# 2_PowerRails.net
KiCad netlist of a schematic drawn in Altium Designer
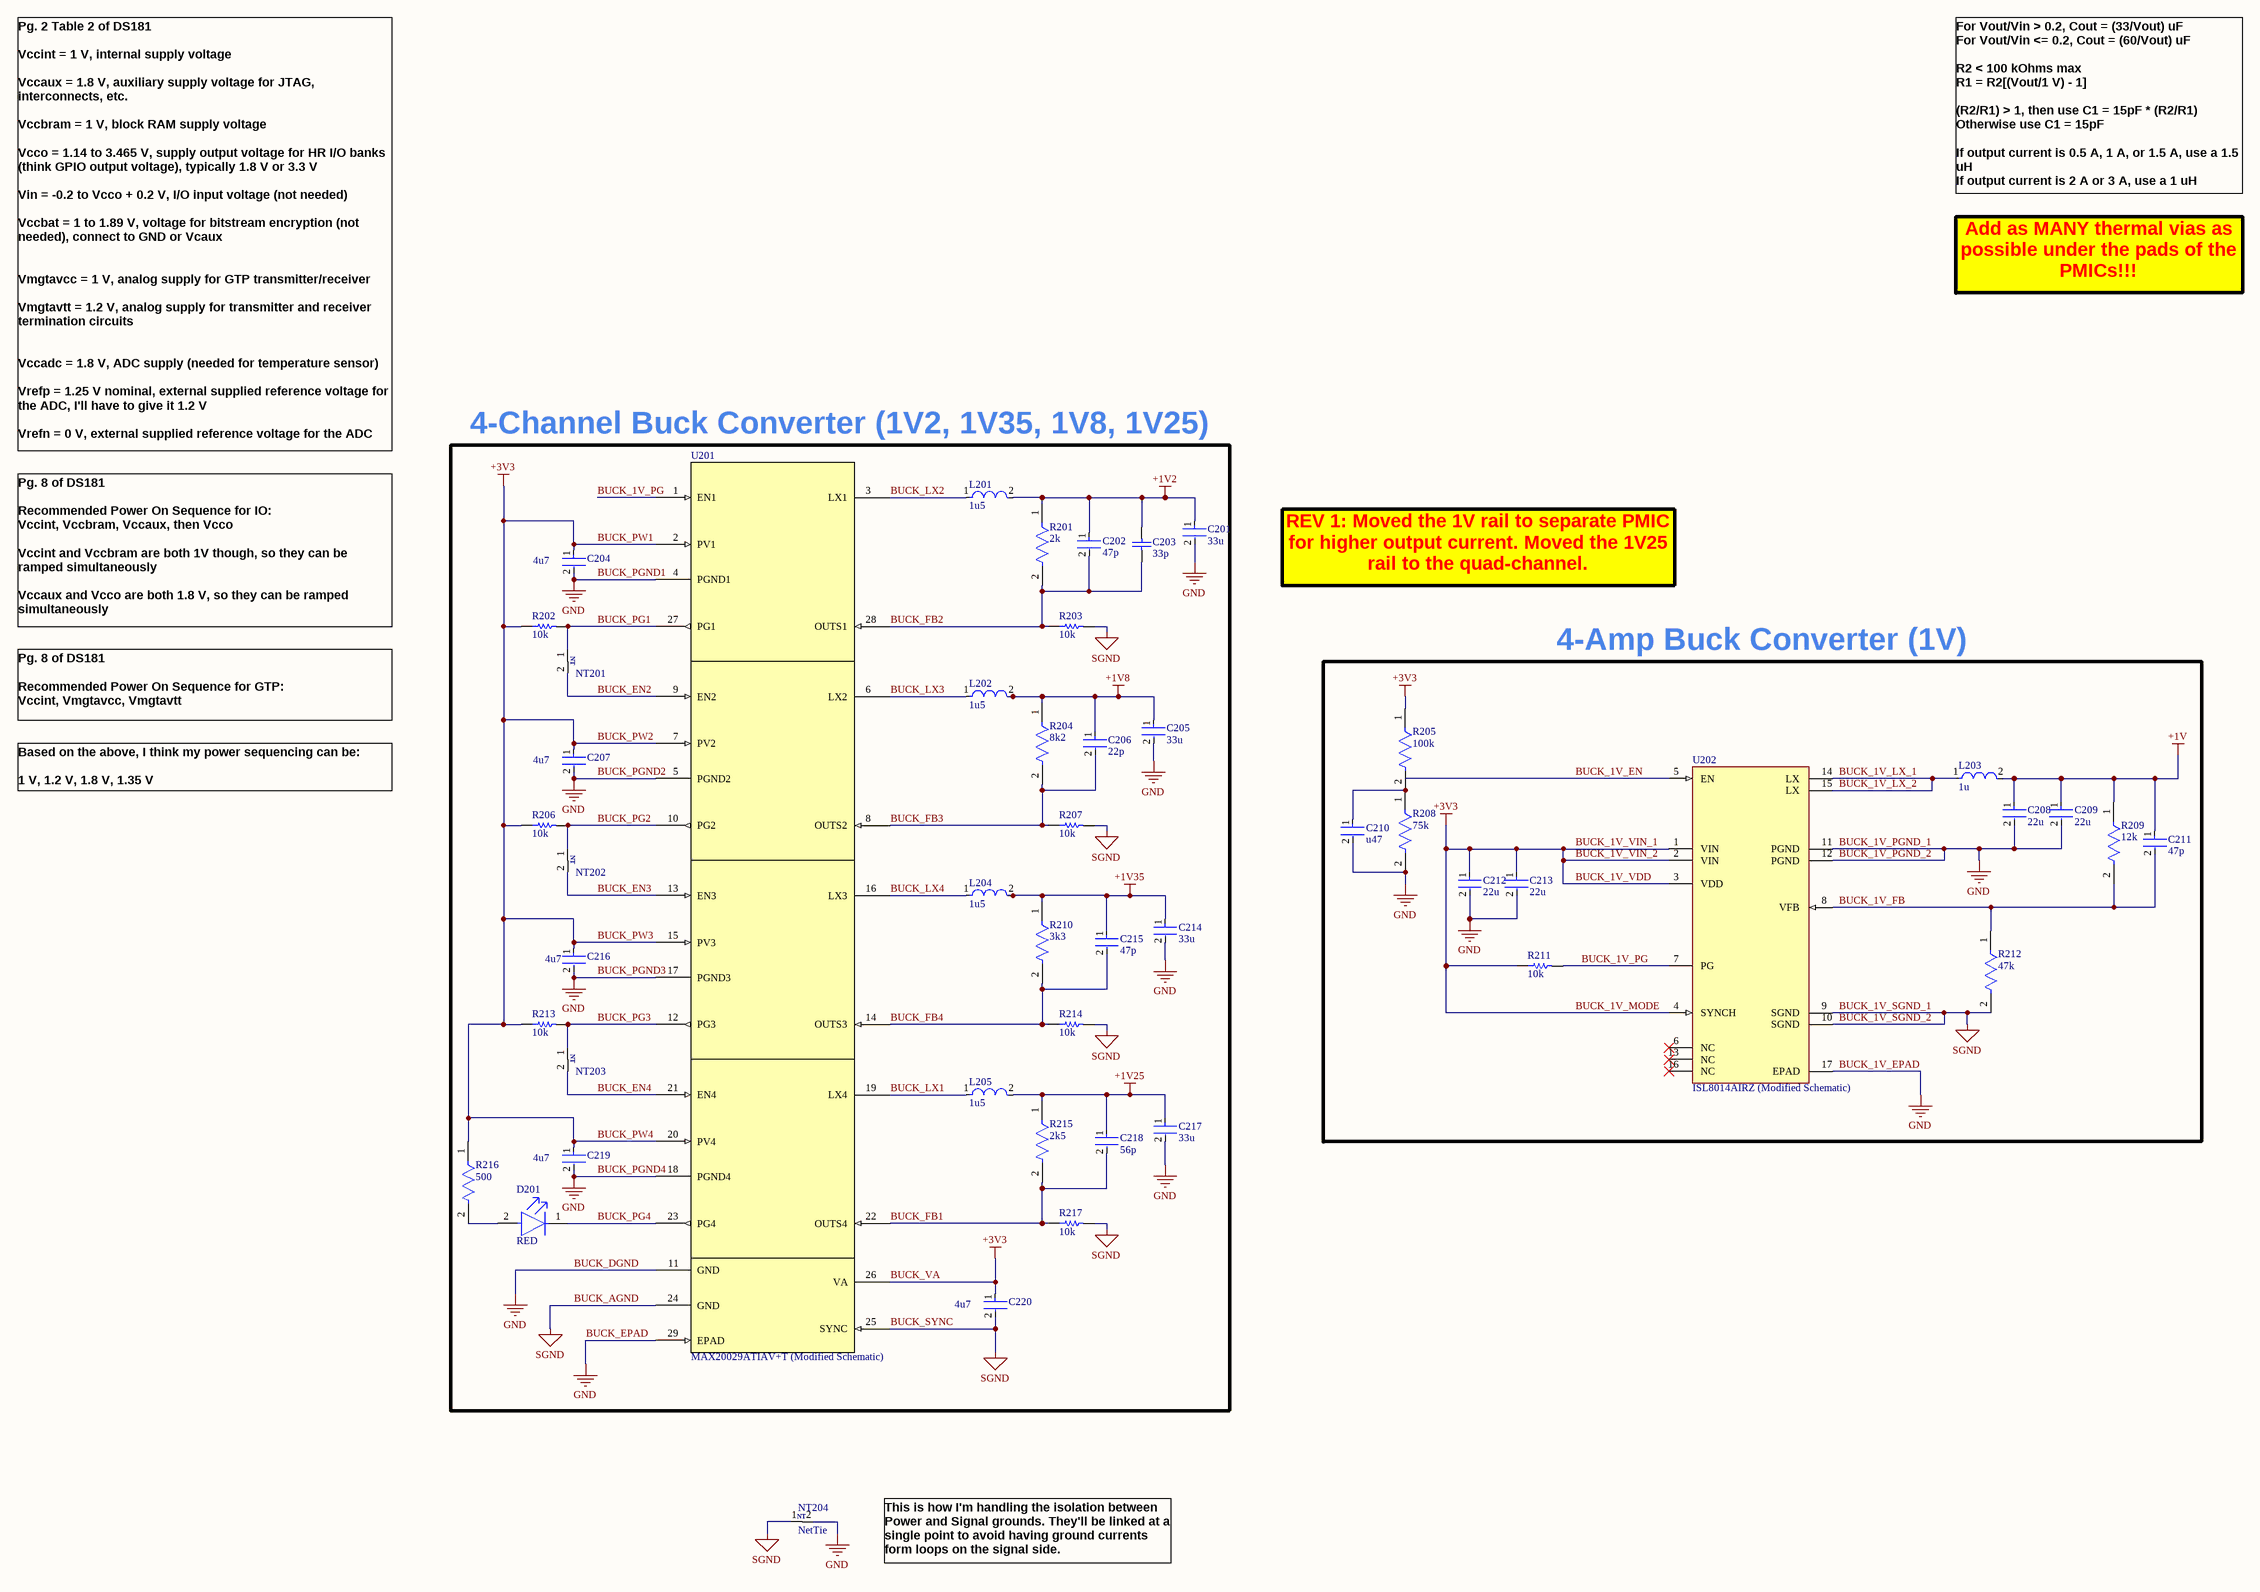
[diagram p0: 2_PowerRails.SchDoc]

(export (version "E")
  (design (tool "Eeschema 10.0.6"))
  (components
    (comp (ref "C201")
      (value "33u")
      (footprint "FP-C2012-125-0_2-IPC_A")
      (description "C2012X5R1A336M125AC\r\n\r\nMultilayer Ceramic Capacitors 33μF ±20% 10V X5R SMD 0805")
      (fields (field (name "TOLERANCE") "20%"))
      (libsource (lib "Altium Content Vault") (part "b4654b650e69147ec39a6b967a45e02"))
    )
    (comp (ref "C202")
      (value "47p")
      (footprint "FP-GCQ155-0_05-MFG")
      (libsource (lib "Altium Content Vault") (part "02cd4be3c70576c341d710602a673aa"))
    )
    (comp (ref "C203")
      (value "33p")
      (footprint "CAPC1005X60X26NL10T16")
      (description "VJ0402A330JXAAC")
      (fields (field (name "MANUFACTURER") "Vitramon"))
      (libsource (lib "Altium Content Vault") (part "CAP"))
    )
    (comp (ref "C204")
      (value "4u7")
      (footprint "FP-GCM31C-0_2-e0_3_0_8-IPC_C")
      (description "GCM31CR71E475KA55K\r\n\r\nCeramic Capacitor for Automotive 4.7uF ±10% 25VDC X7R 1206 Embossed T/R")
      (fields (field (name "TOLERANCE") "10%"))
      (libsource (lib "Altium Content Vault") (part "11868f565c42a9108669ba33697ecf6"))
    )
    (comp (ref "C205")
      (value "33u")
      (footprint "FP-C2012-125-0_2-IPC_A")
      (description "C2012X5R1A336M125AC\r\n\r\nMultilayer Ceramic Capacitors 33μF ±20% 10V X5R SMD 0805")
      (fields (field (name "TOLERANCE") "20%"))
      (libsource (lib "Altium Content Vault") (part "b4654b650e69147ec39a6b967a45e02"))
    )
    (comp (ref "C206")
      (value "22p")
      (footprint "FP-GJM155-0_05-IPC_A")
      (description "GJM1555C1H220GB01D\r\n\r\nMulti-Layer Ceramic Capacitor 22pF C0G  ±2% 0402 Paper T/R")
      (fields (field (name "TOLERANCE") "2%"))
      (libsource (lib "Altium Content Vault") (part "02cd4be3c70576c341d710602a673aa"))
    )
    (comp (ref "C207")
      (value "4u7")
      (footprint "FP-GCM31C-0_2-e0_3_0_8-IPC_C")
      (description "GCM31CR71E475KA55K\r\n\r\nCeramic Capacitor for Automotive 4.7uF ±10% 25VDC X7R 1206 Embossed T/R")
      (fields (field (name "TOLERANCE") "10%"))
      (libsource (lib "Altium Content Vault") (part "11868f565c42a9108669ba33697ecf6"))
    )
    (comp (ref "C208")
      (value "22u")
      (footprint "FP-GRM188-0_2-IPC_A")
      (description "GRM188R61C226ME01D\r\n\r\nMultilayer Ceramic Capacitor 22uF 20% 16V X5R 0603 Paper T/R")
      (libsource (lib "Altium Content Vault") (part "02cd4be3c70576c341d710602a673aa"))
    )
    (comp (ref "C209")
      (value "22u")
      (footprint "FP-GRM188-0_2-IPC_A")
      (description "GRM188R61C226ME01D\r\n\r\nMultilayer Ceramic Capacitor 22uF 20% 16V X5R 0603 Paper T/R")
      (libsource (lib "Altium Content Vault") (part "02cd4be3c70576c341d710602a673aa"))
    )
    (comp (ref "C210")
      (value "u47")
      (footprint "FP-C0603-030-0_03-IPC_A")
      (description "C0603X5R1A474M030BC\r\n\r\nMultilayer Ceramic Capacitors 470nF ±20% 10V X5R SMD 0201")
      (fields (field (name "TOLERANCE") "20%"))
      (libsource (lib "Altium Content Vault") (part "02cd4be3c70576c341d710602a673aa"))
    )
    (comp (ref "C211")
      (value "47p")
      (footprint "FP-GCQ155-0_05-MFG")
      (libsource (lib "Altium Content Vault") (part "02cd4be3c70576c341d710602a673aa"))
    )
    (comp (ref "C212")
      (value "22u")
      (footprint "FP-GRM188-0_2-IPC_A")
      (description "GRM188R61C226ME01D\r\n\r\nMultilayer Ceramic Capacitor 22uF 20% 16V X5R 0603 Paper T/R")
      (libsource (lib "Altium Content Vault") (part "02cd4be3c70576c341d710602a673aa"))
    )
    (comp (ref "C213")
      (value "22u")
      (footprint "FP-GRM188-0_2-IPC_A")
      (description "GRM188R61C226ME01D\r\n\r\nMultilayer Ceramic Capacitor 22uF 20% 16V X5R 0603 Paper T/R")
      (libsource (lib "Altium Content Vault") (part "02cd4be3c70576c341d710602a673aa"))
    )
    (comp (ref "C214")
      (value "33u")
      (footprint "FP-C2012-125-0_2-IPC_A")
      (description "C2012X5R1A336M125AC\r\n\r\nMultilayer Ceramic Capacitors 33μF ±20% 10V X5R SMD 0805")
      (fields (field (name "TOLERANCE") "20%"))
      (libsource (lib "Altium Content Vault") (part "b4654b650e69147ec39a6b967a45e02"))
    )
    (comp (ref "C215")
      (value "47p")
      (footprint "FP-GCQ155-0_05-MFG")
      (libsource (lib "Altium Content Vault") (part "02cd4be3c70576c341d710602a673aa"))
    )
    (comp (ref "C216")
      (value "4u7")
      (footprint "FP-GCM31C-0_2-e0_3_0_8-IPC_C")
      (description "GCM31CR71E475KA55K\r\n\r\nCeramic Capacitor for Automotive 4.7uF ±10% 25VDC X7R 1206 Embossed T/R")
      (fields (field (name "TOLERANCE") "10%"))
      (libsource (lib "Altium Content Vault") (part "11868f565c42a9108669ba33697ecf6"))
    )
    (comp (ref "C217")
      (value "33u")
      (footprint "FP-C2012-125-0_2-IPC_A")
      (description "C2012X5R1A336M125AC\r\n\r\nMultilayer Ceramic Capacitors 33μF ±20% 10V X5R SMD 0805")
      (fields (field (name "TOLERANCE") "20%"))
      (libsource (lib "Altium Content Vault") (part "b4654b650e69147ec39a6b967a45e02"))
    )
    (comp (ref "C218")
      (value "56p")
      (footprint "FP-C0402-BB-MFG")
      (description "C0402 56 pF X8R 10.00% 50 V")
      (fields (field (name "MANUFACTURER PART NUMBER") "C0402C560K5HACTU"))
      (libsource (lib "Altium Content Vault") (part "b4654b650e69147ec39a6b967a45e02"))
    )
    (comp (ref "C219")
      (value "4u7")
      (footprint "FP-GCM31C-0_2-e0_3_0_8-IPC_C")
      (description "GCM31CR71E475KA55K\r\n\r\nCeramic Capacitor for Automotive 4.7uF ±10% 25VDC X7R 1206 Embossed T/R")
      (fields (field (name "TOLERANCE") "10%"))
      (libsource (lib "Altium Content Vault") (part "11868f565c42a9108669ba33697ecf6"))
    )
    (comp (ref "C220")
      (value "4u7")
      (footprint "FP-GCM31C-0_2-e0_3_0_8-IPC_C")
      (description "GCM31CR71E475KA55K\r\n\r\nCeramic Capacitor for Automotive 4.7uF ±10% 25VDC X7R 1206 Embossed T/R")
      (fields (field (name "TOLERANCE") "10%"))
      (libsource (lib "Altium Content Vault") (part "11868f565c42a9108669ba33697ecf6"))
    )
    (comp (ref "D201")
      (value "RED")
      (footprint "FP-SML-LX0603SIW-TR-MFG")
      (description "SML-LX0603SIW-TR\r\n\r\nLED RED DIFFUSED SMD")
      (libsource (lib "Altium Content Vault") (part "8706943c75ba83719d021d2fdc84c58"))
    )
    (comp (ref "L201")
      (value "1u5")
      (footprint "FP-IHLP-2525CZ-FP_2_413x3-MFG")
      (fields (field (name "TOLERANCE") "20%"))
      (libsource (lib "Altium Content Vault") (part "725321dda6339637d4d059423bc1c3c"))
    )
    (comp (ref "L202")
      (value "1u5")
      (footprint "FP-IHLP-2525CZ-FP_2_413x3-MFG")
      (fields (field (name "TOLERANCE") "20%"))
      (libsource (lib "Altium Content Vault") (part "725321dda6339637d4d059423bc1c3c"))
    )
    (comp (ref "L203")
      (value "1u")
      (footprint "FP-IHLP-2525CZ-FP_2_413x3-MFG")
      (fields (field (name "TOLERANCE") "20%"))
      (libsource (lib "Altium Content Vault") (part "725321dda6339637d4d059423bc1c3c"))
    )
    (comp (ref "L204")
      (value "1u5")
      (footprint "FP-IHLP-2525CZ-FP_2_413x3-MFG")
      (fields (field (name "TOLERANCE") "20%"))
      (libsource (lib "Altium Content Vault") (part "725321dda6339637d4d059423bc1c3c"))
    )
    (comp (ref "L205")
      (value "1u5")
      (footprint "FP-IHLP-2525CZ-FP_2_413x3-MFG")
      (fields (field (name "TOLERANCE") "20%"))
      (libsource (lib "Altium Content Vault") (part "725321dda6339637d4d059423bc1c3c"))
    )
    (comp (ref "NT201")
      (value "NetTie")
      (footprint "NETTIE")
      (description "Net Tie")
      (fields (field (name "SOURCE") "Schematic-Lib-PhilsLab.SchLib"))
      (libsource (lib "Withanage Perera") (part "NetTie"))
    )
    (comp (ref "NT202")
      (value "NetTie")
      (footprint "NETTIE")
      (description "Net Tie")
      (fields (field (name "SOURCE") "Schematic-Lib-PhilsLab.SchLib"))
      (libsource (lib "Withanage Perera") (part "NetTie"))
    )
    (comp (ref "NT203")
      (value "NetTie")
      (footprint "NETTIE")
      (description "Net Tie")
      (fields (field (name "SOURCE") "Schematic-Lib-PhilsLab.SchLib"))
      (libsource (lib "Withanage Perera") (part "NetTie"))
    )
    (comp (ref "NT204")
      (value "NetTie")
      (footprint "NETTIE")
      (description "Net Tie")
      (fields (field (name "SOURCE") "Schematic-Lib-PhilsLab.SchLib"))
      (libsource (lib "Withanage Perera") (part "NetTie"))
    )
    (comp (ref "R201")
      (value "2k")
      (footprint "FP-MCS0402-IPC_A")
      (description "MCS0402MD2001BE100\r\n\r\nRES SMD 1.2K OHM 1% 1/10W 0402")
      (fields (field (name "TOLERANCE") "0.1%"))
      (libsource (lib "Altium Content Vault") (part "1029c3af85768c4190bb7ad29bc67b5"))
    )
    (comp (ref "R202")
      (value "10k")
      (footprint "RESC1005X40X25LL10T10")
      (description "SG73P1ETTP1002F")
      (fields (field (name "MANUFACTURER") "KOA Speer"))
      (libsource (lib "Altium Content Vault") (part "RES"))
    )
    (comp (ref "R203")
      (value "10k")
      (footprint "RESC1005X40X25LL10T10")
      (description "SG73P1ETTP1002F")
      (fields (field (name "MANUFACTURER") "KOA Speer"))
      (libsource (lib "Altium Content Vault") (part "RES"))
    )
    (comp (ref "R204")
      (value "8k2")
      (footprint "FP-ERA2A-MFG")
      (description "ERA-2AEB822X\r\n\r\nRES SMD 8.2K OHM 0.1% 1/16W 0402")
      (fields
        (field (name "MANUFACTURER") "Panasonic Electronic Components")
        (field (name "OCTOPART") "https://octopart.com/era-2aeb822x-panasonic-43284358")
      )
      (libsource (lib "Altium Content Vault") (part "1029c3af85768c4190bb7ad29bc67b5"))
    )
    (comp (ref "R205")
      (value "100k")
      (footprint "FP-MCS0402-MFG")
      (description "MCS04020D1003BE000\r\n\r\nRES SMD 1.2K OHM 1% 1/10W 0402")
      (fields (field (name "TOLERANCE") "0.1%"))
      (libsource (lib "Altium Content Vault") (part "1029c3af85768c4190bb7ad29bc67b5"))
    )
    (comp (ref "R206")
      (value "10k")
      (footprint "RESC1005X40X25LL10T10")
      (description "SG73P1ETTP1002F")
      (fields (field (name "MANUFACTURER") "KOA Speer"))
      (libsource (lib "Altium Content Vault") (part "RES"))
    )
    (comp (ref "R207")
      (value "10k")
      (footprint "RESC1005X40X25LL10T10")
      (description "SG73P1ETTP1002F")
      (fields (field (name "MANUFACTURER") "KOA Speer"))
      (libsource (lib "Altium Content Vault") (part "RES"))
    )
    (comp (ref "R208")
      (value "75k")
      (footprint "FP-CR0402-IPC_C")
      (description "CR0402-FX-7502GLF\r\n\r\nThick Film Chip Resistors 0402 75kΩ 0.0625W 1% 100ppm/°C")
      (fields (field (name "TOLERANCE") "1%"))
      (libsource (lib "Altium Content Vault") (part "1029c3af85768c4190bb7ad29bc67b5"))
    )
    (comp (ref "R209")
      (value "12k")
      (footprint "FP-RT0402-MFG")
      (description "RT0402 12KΩ 0.063W 50 ppm/°C 0.50%")
      (fields (field (name "OCTOPART") "https://octopart.com/rt0402dre0712kl-yageo-1393491"))
      (libsource (lib "Altium Content Vault") (part "1029c3af85768c4190bb7ad29bc67b5"))
    )
    (comp (ref "R210")
      (value "3k3")
      (footprint "FP-ERA2A-MFG")
      (description "ERA-2AEB332X")
      (fields (field (name "TOLERANCE") "0.1%"))
      (libsource (lib "Altium Content Vault") (part "1029c3af85768c4190bb7ad29bc67b5"))
    )
    (comp (ref "R211")
      (value "10k")
      (footprint "RESC1005X40X25LL10T10")
      (description "SG73P1ETTP1002F")
      (fields (field (name "MANUFACTURER") "KOA Speer"))
      (libsource (lib "Altium Content Vault") (part "RES"))
    )
    (comp (ref "R212")
      (value "47k")
      (footprint "FP-ERA2A-MFG")
      (description "ERA-2AEB473X")
      (fields (field (name "TOLERANCE") "0.1%"))
      (libsource (lib "Altium Content Vault") (part "1029c3af85768c4190bb7ad29bc67b5"))
    )
    (comp (ref "R213")
      (value "10k")
      (footprint "RESC1005X40X25LL10T10")
      (description "SG73P1ETTP1002F")
      (fields (field (name "MANUFACTURER") "KOA Speer"))
      (libsource (lib "Altium Content Vault") (part "RES"))
    )
    (comp (ref "R214")
      (value "10k")
      (footprint "RESC1005X40X25LL10T10")
      (description "SG73P1ETTP1002F")
      (fields (field (name "MANUFACTURER") "KOA Speer"))
      (libsource (lib "Altium Content Vault") (part "RES"))
    )
    (comp (ref "R215")
      (value "2k5")
      (footprint "FP-MCT0603-MFG")
      (description "MCT06030E2501BP100\r\n\r\nRES SMD 100 OHM 1% 1/8W 0603")
      (fields (field (name "TOLERANCE") "0.1%"))
      (libsource (lib "Altium Content Vault") (part "1029c3af85768c4190bb7ad29bc67b5"))
    )
    (comp (ref "R216")
      (value "500")
      (footprint "FP-PNM0402-MFG")
      (description "PNM0402E5000BST1\r\n\r\nRES SMD 500 OHM 0.1% 1/20W 0402")
      (fields (field (name "TOLERANCE") "0.1%"))
      (libsource (lib "Altium Content Vault") (part "1029c3af85768c4190bb7ad29bc67b5"))
    )
    (comp (ref "R217")
      (value "10k")
      (footprint "RESC1005X40X25LL10T10")
      (description "SG73P1ETTP1002F")
      (fields (field (name "MANUFACTURER") "KOA Speer"))
      (libsource (lib "Altium Content Vault") (part "RES"))
    )
    (comp (ref "U201")
      (value "MAX20029ATIAV+T (Modified Schematic)")
      (footprint "21-0140L_T2855-5_MXM")
      (description "Automotive Quad/Triple Low-Voltage Step-Down DC-DC Converters")
      (fields
        (field (name "MANUFACTURER_PART_NUMBER") "MAX20029ATIA/V+T")
        (field (name "COPYRIGHT") "Copyright (C) 2025 Ultra Librarian. All rights reserved.")
      )
      (libsource (lib "Withanage Perera") (part "MAX20029ATIAV+T"))
    )
    (comp (ref "U202")
      (value "ISL8014AIRZ (Modified Schematic)")
      (footprint "QFN65P400X400X100-17_L16_4x4_M")
      (description "ISL8014 Series 2.8 - 5.5 V 1 MHz 4 A Buck Regulator - QFN-16")
      (libsource (lib "Withanage Perera") (part "6273e654be0da227d358b1ef3a404fb"))
    )
  )
  (nets
    (net (code "1") (name "+1V") (class "Default")
      (node (ref "C208") (pin "1") (pinfunction "1_1") (pintype "passive"))
      (node (ref "C209") (pin "1") (pinfunction "1_1") (pintype "passive"))
      (node (ref "C211") (pin "1") (pinfunction "1_1") (pintype "passive"))
      (node (ref "L203") (pin "2") (pinfunction "2_2") (pintype "passive"))
      (node (ref "R209") (pin "1") (pinfunction "1_1") (pintype "passive"))
    )
    (net (code "2") (name "+1V2") (class "Default")
      (node (ref "C201") (pin "1") (pinfunction "1_1") (pintype "passive"))
      (node (ref "C202") (pin "1") (pinfunction "1_1") (pintype "passive"))
      (node (ref "C203") (pin "2") (pinfunction "2_2") (pintype "passive"))
      (node (ref "L201") (pin "2") (pinfunction "2_2") (pintype "passive"))
      (node (ref "R201") (pin "1") (pinfunction "1_1") (pintype "passive"))
    )
    (net (code "3") (name "+1V8") (class "Default")
      (node (ref "C205") (pin "1") (pinfunction "1_1") (pintype "passive"))
      (node (ref "C206") (pin "1") (pinfunction "1_1") (pintype "passive"))
      (node (ref "L202") (pin "2") (pinfunction "2_2") (pintype "passive"))
      (node (ref "R204") (pin "1") (pinfunction "1_1") (pintype "passive"))
    )
    (net (code "4") (name "+1V25") (class "Default")
      (node (ref "C217") (pin "1") (pinfunction "1_1") (pintype "passive"))
      (node (ref "C218") (pin "1") (pinfunction "1_1") (pintype "passive"))
      (node (ref "L205") (pin "2") (pinfunction "2_2") (pintype "passive"))
      (node (ref "R215") (pin "1") (pinfunction "1_1") (pintype "passive"))
    )
    (net (code "5") (name "+1V35") (class "Default")
      (node (ref "C214") (pin "1") (pinfunction "1_1") (pintype "passive"))
      (node (ref "C215") (pin "1") (pinfunction "1_1") (pintype "passive"))
      (node (ref "L204") (pin "2") (pinfunction "2_2") (pintype "passive"))
      (node (ref "R210") (pin "1") (pinfunction "1_1") (pintype "passive"))
    )
    (net (code "6") (name "+3V3") (class "Default")
      (node (ref "C204") (pin "1") (pinfunction "1_1") (pintype "passive"))
      (node (ref "C207") (pin "1") (pinfunction "1_1") (pintype "passive"))
      (node (ref "C212") (pin "1") (pinfunction "1_1") (pintype "passive"))
      (node (ref "C213") (pin "1") (pinfunction "1_1") (pintype "passive"))
      (node (ref "C216") (pin "1") (pinfunction "1_1") (pintype "passive"))
      (node (ref "C219") (pin "1") (pinfunction "1_1") (pintype "passive"))
      (node (ref "C220") (pin "1") (pinfunction "1_1") (pintype "passive"))
      (node (ref "R202") (pin "1") (pinfunction "1_1") (pintype "passive"))
      (node (ref "R205") (pin "1") (pinfunction "1_1") (pintype "passive"))
      (node (ref "R206") (pin "1") (pinfunction "1_1") (pintype "passive"))
      (node (ref "R211") (pin "1") (pinfunction "1_1") (pintype "passive"))
      (node (ref "R213") (pin "1") (pinfunction "1_1") (pintype "passive"))
      (node (ref "R216") (pin "1") (pinfunction "1_1") (pintype "passive"))
      (node (ref "U201") (pin "15") (pinfunction "PV3_15") (pintype "input"))
      (node (ref "U201") (pin "2") (pinfunction "PV1_2") (pintype "input"))
      (node (ref "U201") (pin "20") (pinfunction "PV4_20") (pintype "input"))
      (node (ref "U201") (pin "26") (pinfunction "VA_26") (pintype "passive"))
      (node (ref "U201") (pin "7") (pinfunction "PV2_7") (pintype "input"))
      (node (ref "U202") (pin "1") (pinfunction "VIN_1") (pintype "power_in"))
      (node (ref "U202") (pin "2") (pinfunction "VIN_2") (pintype "power_in"))
      (node (ref "U202") (pin "3") (pinfunction "VDD_3") (pintype "power_in"))
      (node (ref "U202") (pin "4") (pinfunction "SYNCH_4") (pintype "input"))
    )
    (net (code "7") (name "/BUCK_1V_EN") (class "Default")
      (node (ref "U202") (pin "5") (pinfunction "EN_5") (pintype "input"))
    )
    (net (code "8") (name "/BUCK_1V_FB") (class "Default")
      (node (ref "C211") (pin "2") (pinfunction "2_2") (pintype "passive"))
      (node (ref "R209") (pin "2") (pinfunction "2_2") (pintype "passive"))
      (node (ref "R212") (pin "1") (pinfunction "1_1") (pintype "passive"))
      (node (ref "U202") (pin "8") (pinfunction "VFB_8") (pintype "input"))
    )
    (net (code "9") (name "/BUCK_1V_LX_1") (class "Default")
      (node (ref "L203") (pin "1") (pinfunction "1_1") (pintype "passive"))
      (node (ref "U202") (pin "14") (pinfunction "LX_14") (pintype "passive"))
      (node (ref "U202") (pin "15") (pinfunction "LX_15") (pintype "passive"))
    )
    (net (code "10") (name "/BUCK_1V_PG") (class "Default")
      (node (ref "R211") (pin "2") (pinfunction "2_2") (pintype "passive"))
      (node (ref "U201") (pin "1") (pinfunction "EN1_1") (pintype "input"))
      (node (ref "U202") (pin "7") (pinfunction "PG_7") (pintype "open_collector"))
    )
    (net (code "11") (name "/BUCK_EN2") (class "Default")
      (node (ref "NT201") (pin "2") (pinfunction "2_2") (pintype "passive"))
      (node (ref "U201") (pin "9") (pinfunction "EN2_9") (pintype "input"))
    )
    (net (code "12") (name "/BUCK_EN3") (class "Default")
      (node (ref "NT202") (pin "2") (pinfunction "2_2") (pintype "passive"))
      (node (ref "U201") (pin "13") (pinfunction "EN3_13") (pintype "input"))
    )
    (net (code "13") (name "/BUCK_EN4") (class "Default")
      (node (ref "NT203") (pin "2") (pinfunction "2_2") (pintype "passive"))
      (node (ref "U201") (pin "21") (pinfunction "EN4_21") (pintype "input"))
    )
    (net (code "14") (name "/BUCK_FB1") (class "Default")
      (node (ref "C218") (pin "2") (pinfunction "2_2") (pintype "passive"))
      (node (ref "R215") (pin "2") (pinfunction "2_2") (pintype "passive"))
      (node (ref "R217") (pin "1") (pinfunction "1_1") (pintype "passive"))
      (node (ref "U201") (pin "22") (pinfunction "OUTS4_22") (pintype "input"))
    )
    (net (code "15") (name "/BUCK_FB2") (class "Default")
      (node (ref "C202") (pin "2") (pinfunction "2_2") (pintype "passive"))
      (node (ref "C203") (pin "1") (pinfunction "1_1") (pintype "passive"))
      (node (ref "R201") (pin "2") (pinfunction "2_2") (pintype "passive"))
      (node (ref "R203") (pin "1") (pinfunction "1_1") (pintype "passive"))
      (node (ref "U201") (pin "28") (pinfunction "OUTS1_28") (pintype "input"))
    )
    (net (code "16") (name "/BUCK_FB3") (class "Default")
      (node (ref "C206") (pin "2") (pinfunction "2_2") (pintype "passive"))
      (node (ref "R204") (pin "2") (pinfunction "2_2") (pintype "passive"))
      (node (ref "R207") (pin "1") (pinfunction "1_1") (pintype "passive"))
      (node (ref "U201") (pin "8") (pinfunction "OUTS2_8") (pintype "input"))
    )
    (net (code "17") (name "/BUCK_FB4") (class "Default")
      (node (ref "C215") (pin "2") (pinfunction "2_2") (pintype "passive"))
      (node (ref "R210") (pin "2") (pinfunction "2_2") (pintype "passive"))
      (node (ref "R214") (pin "1") (pinfunction "1_1") (pintype "passive"))
      (node (ref "U201") (pin "14") (pinfunction "OUTS3_14") (pintype "input"))
    )
    (net (code "18") (name "/BUCK_LX1") (class "Default")
      (node (ref "L205") (pin "1") (pinfunction "1_1") (pintype "passive"))
      (node (ref "U201") (pin "19") (pinfunction "LX4_19") (pintype "passive"))
    )
    (net (code "19") (name "/BUCK_LX2") (class "Default")
      (node (ref "L201") (pin "1") (pinfunction "1_1") (pintype "passive"))
      (node (ref "U201") (pin "3") (pinfunction "LX1_3") (pintype "passive"))
    )
    (net (code "20") (name "/BUCK_LX3") (class "Default")
      (node (ref "L202") (pin "1") (pinfunction "1_1") (pintype "passive"))
      (node (ref "U201") (pin "6") (pinfunction "LX2_6") (pintype "passive"))
    )
    (net (code "21") (name "/BUCK_LX4") (class "Default")
      (node (ref "L204") (pin "1") (pinfunction "1_1") (pintype "passive"))
      (node (ref "U201") (pin "16") (pinfunction "LX3_16") (pintype "passive"))
    )
    (net (code "22") (name "/BUCK_PG1") (class "Default")
      (node (ref "NT201") (pin "1") (pinfunction "1_1") (pintype "passive"))
      (node (ref "R202") (pin "2") (pinfunction "2_2") (pintype "passive"))
      (node (ref "U201") (pin "27") (pinfunction "PG1_27") (pintype "output"))
    )
    (net (code "23") (name "/BUCK_PG2") (class "Default")
      (node (ref "NT202") (pin "1") (pinfunction "1_1") (pintype "passive"))
      (node (ref "R206") (pin "2") (pinfunction "2_2") (pintype "passive"))
      (node (ref "U201") (pin "10") (pinfunction "PG2_10") (pintype "output"))
    )
    (net (code "24") (name "/BUCK_PG3") (class "Default")
      (node (ref "NT203") (pin "1") (pinfunction "1_1") (pintype "passive"))
      (node (ref "R213") (pin "2") (pinfunction "2_2") (pintype "passive"))
      (node (ref "U201") (pin "12") (pinfunction "PG3_12") (pintype "output"))
    )
    (net (code "25") (name "/BUCK_PG4") (class "Default")
      (node (ref "D201") (pin "1") (pinfunction "C_1") (pintype "passive"))
      (node (ref "U201") (pin "23") (pinfunction "PG4_23") (pintype "output"))
    )
    (net (code "26") (name "GND") (class "Default")
      (node (ref "C201") (pin "2") (pinfunction "2_2") (pintype "passive"))
      (node (ref "C204") (pin "2") (pinfunction "2_2") (pintype "passive"))
      (node (ref "C205") (pin "2") (pinfunction "2_2") (pintype "passive"))
      (node (ref "C207") (pin "2") (pinfunction "2_2") (pintype "passive"))
      (node (ref "C208") (pin "2") (pinfunction "2_2") (pintype "passive"))
      (node (ref "C209") (pin "2") (pinfunction "2_2") (pintype "passive"))
      (node (ref "C210") (pin "2") (pinfunction "2_2") (pintype "passive"))
      (node (ref "C212") (pin "2") (pinfunction "2_2") (pintype "passive"))
      (node (ref "C213") (pin "2") (pinfunction "2_2") (pintype "passive"))
      (node (ref "C214") (pin "2") (pinfunction "2_2") (pintype "passive"))
      (node (ref "C216") (pin "2") (pinfunction "2_2") (pintype "passive"))
      (node (ref "C217") (pin "2") (pinfunction "2_2") (pintype "passive"))
      (node (ref "C219") (pin "2") (pinfunction "2_2") (pintype "passive"))
      (node (ref "NT204") (pin "2") (pinfunction "2_2") (pintype "passive"))
      (node (ref "R208") (pin "2") (pinfunction "2_2") (pintype "passive"))
      (node (ref "U201") (pin "11") (pinfunction "GND_11") (pintype "power_in"))
      (node (ref "U201") (pin "17") (pinfunction "PGND3_17") (pintype "power_in"))
      (node (ref "U201") (pin "18") (pinfunction "PGND4_18") (pintype "power_in"))
      (node (ref "U201") (pin "29") (pinfunction "EPAD_29") (pintype "input"))
      (node (ref "U201") (pin "4") (pinfunction "PGND1_4") (pintype "power_in"))
      (node (ref "U201") (pin "5") (pinfunction "PGND2_5") (pintype "power_in"))
      (node (ref "U202") (pin "11") (pinfunction "PGND_11") (pintype "power_in"))
      (node (ref "U202") (pin "12") (pinfunction "PGND_12") (pintype "power_in"))
      (node (ref "U202") (pin "17") (pinfunction "EPAD_17") (pintype "power_in"))
    )
    (net (code "27") (name "Net-(C210-Pad1)") (class "Default")
      (node (ref "C210") (pin "1") (pinfunction "1_1") (pintype "passive"))
      (node (ref "R205") (pin "2") (pinfunction "2_2") (pintype "passive"))
      (node (ref "R208") (pin "1") (pinfunction "1_1") (pintype "passive"))
    )
    (net (code "28") (name "Net-(D201-A)") (class "Default")
      (node (ref "D201") (pin "2") (pinfunction "A_2") (pintype "passive"))
      (node (ref "R216") (pin "2") (pinfunction "2_2") (pintype "passive"))
    )
    (net (code "29") (name "SGND") (class "Default")
      (node (ref "C220") (pin "2") (pinfunction "2_2") (pintype "passive"))
      (node (ref "NT204") (pin "1") (pinfunction "1_1") (pintype "passive"))
      (node (ref "R203") (pin "2") (pinfunction "2_2") (pintype "passive"))
      (node (ref "R207") (pin "2") (pinfunction "2_2") (pintype "passive"))
      (node (ref "R212") (pin "2") (pinfunction "2_2") (pintype "passive"))
      (node (ref "R214") (pin "2") (pinfunction "2_2") (pintype "passive"))
      (node (ref "R217") (pin "2") (pinfunction "2_2") (pintype "passive"))
      (node (ref "U201") (pin "24") (pinfunction "GND_24") (pintype "power_in"))
      (node (ref "U201") (pin "25") (pinfunction "SYNC_25") (pintype "input"))
      (node (ref "U202") (pin "10") (pinfunction "SGND_10") (pintype "power_in"))
      (node (ref "U202") (pin "9") (pinfunction "SGND_9") (pintype "power_in"))
    )
    (net (code "30") (name "unconnected-(U202-NC-Pad6)") (class "Default")
      (node (ref "U202") (pin "6") (pinfunction "NC_6") (pintype "passive+no_connect"))
    )
    (net (code "31") (name "unconnected-(U202-NC-Pad13)") (class "Default")
      (node (ref "U202") (pin "13") (pinfunction "NC_13") (pintype "passive+no_connect"))
    )
    (net (code "32") (name "unconnected-(U202-NC-Pad16)") (class "Default")
      (node (ref "U202") (pin "16") (pinfunction "NC_16") (pintype "passive+no_connect"))
    )
  )
)
